# RDF-600.net
KiCad netlist of a schematic drawn in EAGLE
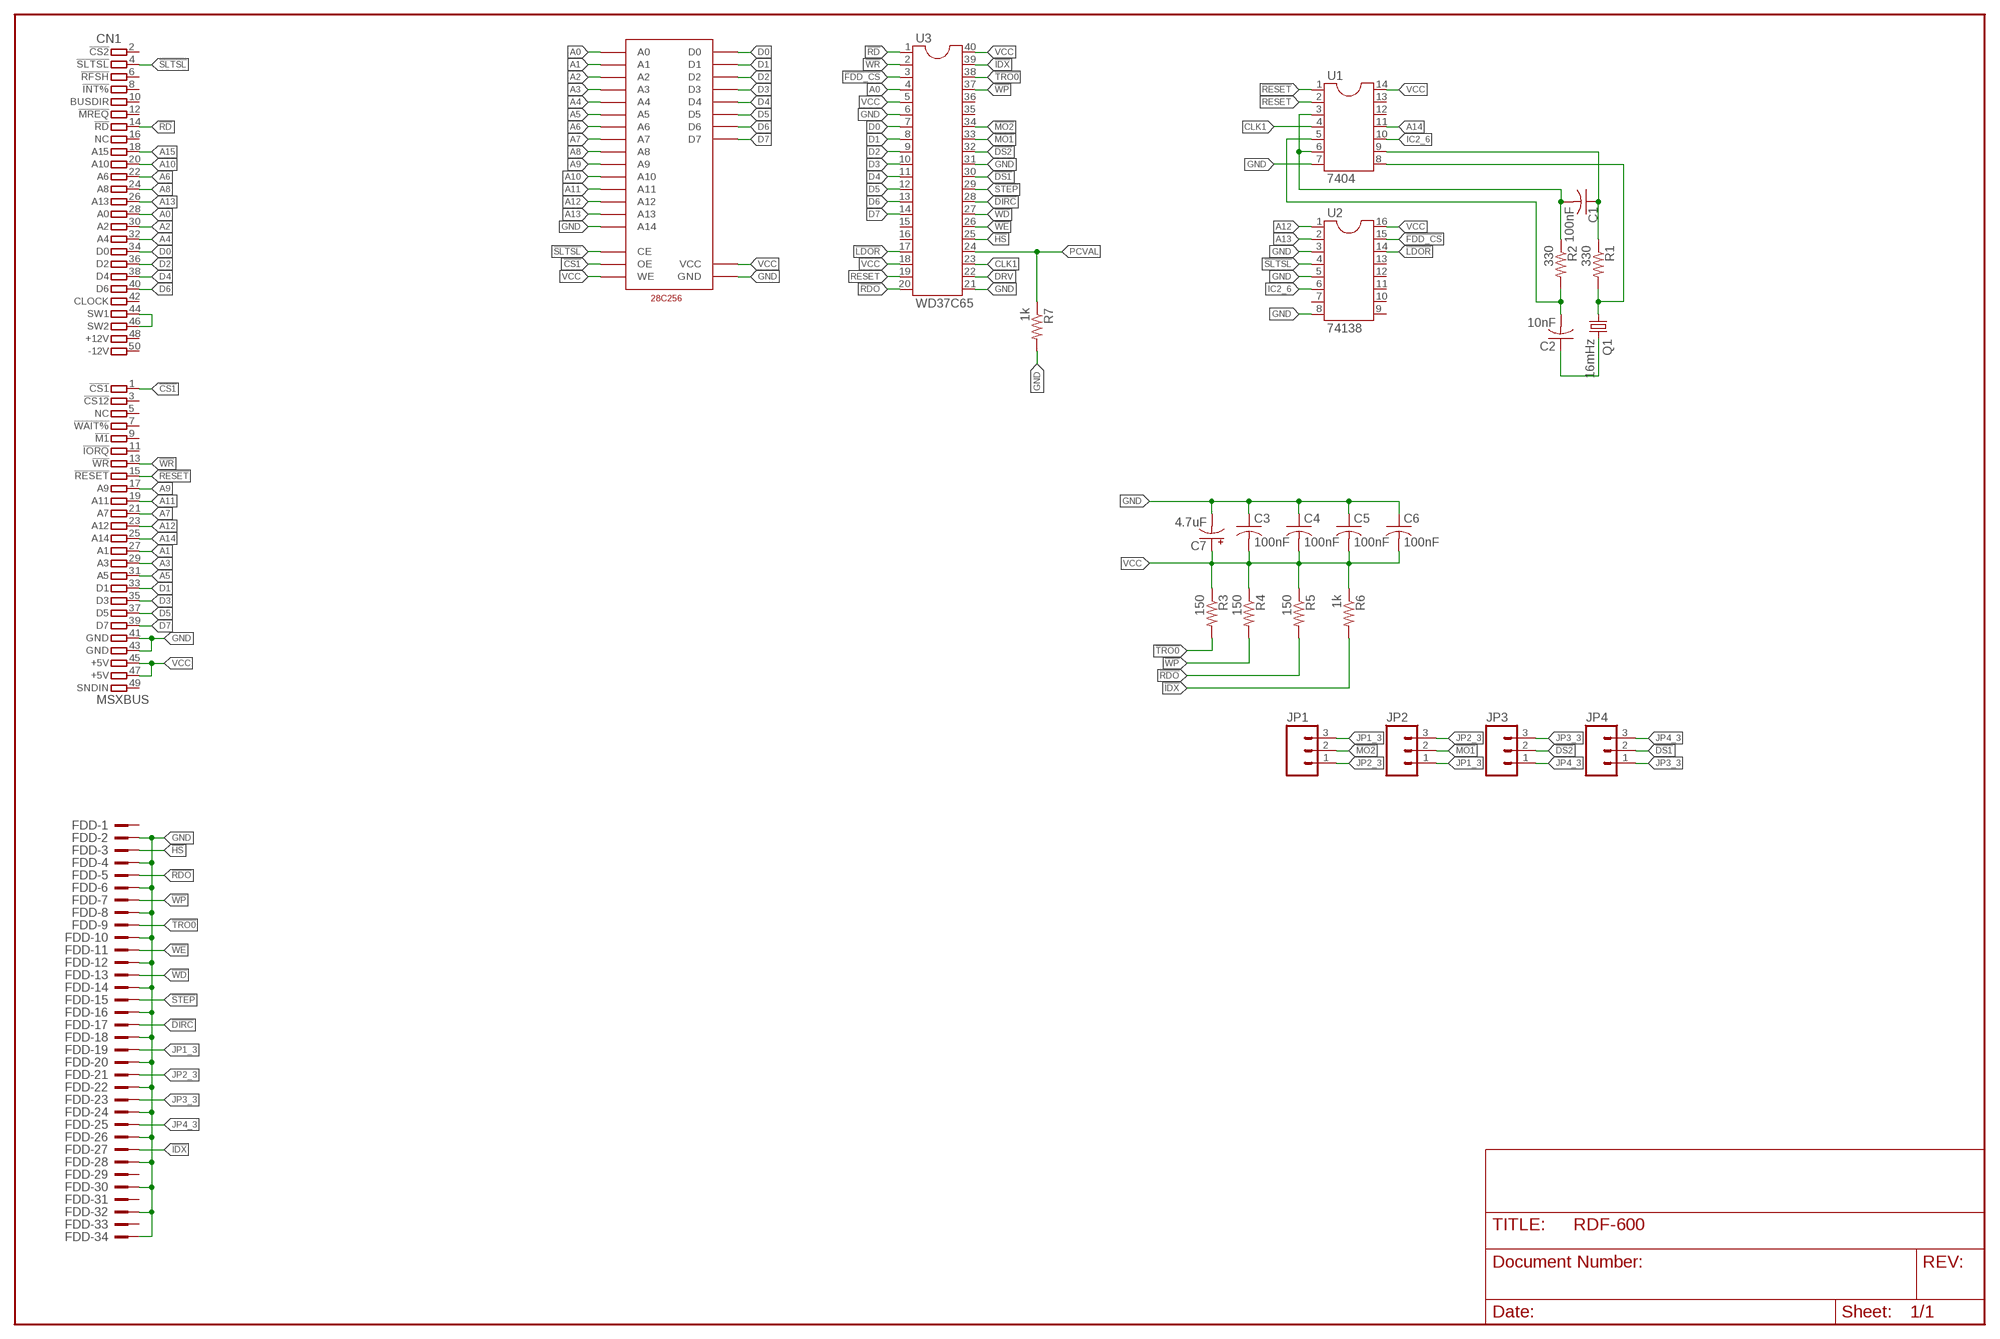
[diagram p0: schematic, sheet 1]

(export (version "E")
  (design (tool "Eeschema 10.0.6"))
  (components
    (comp (ref "28C256")
      (value "28C256")
      (footprint "eagle-import:DIP28")
      (libsource (lib "eagle-import") (part "28C256"))
    )
    (comp (ref "C1")
      (value "100nF")
      (footprint "eagle-import:C025-025X050")
      (libsource (lib "eagle-import") (part "C-US025-025X050"))
    )
    (comp (ref "C2")
      (value "10nF")
      (footprint "eagle-import:C025-025X050")
      (libsource (lib "eagle-import") (part "C-US025-025X050"))
    )
    (comp (ref "C3")
      (value "100nF")
      (footprint "eagle-import:C025-025X050")
      (libsource (lib "eagle-import") (part "C-US025-025X050"))
    )
    (comp (ref "C4")
      (value "100nF")
      (footprint "eagle-import:C025-025X050")
      (libsource (lib "eagle-import") (part "C-US025-025X050"))
    )
    (comp (ref "C5")
      (value "100nF")
      (footprint "eagle-import:C025-025X050")
      (libsource (lib "eagle-import") (part "C-US025-025X050"))
    )
    (comp (ref "C6")
      (value "100nF")
      (footprint "eagle-import:C025-025X050")
      (libsource (lib "eagle-import") (part "C-US025-025X050"))
    )
    (comp (ref "C7")
      (value "4.7uF")
      (footprint "eagle-import:E2,5-6E")
      (libsource (lib "eagle-import") (part "CPOL-USE2,5-6E"))
    )
    (comp (ref "CN1")
      (value "MSXBUS")
      (footprint "eagle-import:MSXBUS_EDGECONN")
      (libsource (lib "eagle-import") (part "MSXBUS_EDGE"))
    )
    (comp (ref "FDD")
      (value "2534-5")
      (footprint "eagle-import:PAK100_2500-5-34")
      (libsource (lib "eagle-import") (part "2534-5"))
    )
    (comp (ref "JP1")
      (value "M03PTH")
      (footprint "eagle-import:1X03")
      (libsource (lib "eagle-import") (part "M03PTH"))
    )
    (comp (ref "JP2")
      (value "M03PTH")
      (footprint "eagle-import:1X03")
      (libsource (lib "eagle-import") (part "M03PTH"))
    )
    (comp (ref "JP3")
      (value "M03PTH")
      (footprint "eagle-import:1X03")
      (libsource (lib "eagle-import") (part "M03PTH"))
    )
    (comp (ref "JP4")
      (value "M03PTH")
      (footprint "eagle-import:1X03")
      (libsource (lib "eagle-import") (part "M03PTH"))
    )
    (comp (ref "Q1")
      (value "16mHz")
      (footprint "eagle-import:HC49_S")
      (libsource (lib "eagle-import") (part "CRYSTALHC49S"))
    )
    (comp (ref "R1")
      (value "330")
      (footprint "eagle-import:0207_7")
      (libsource (lib "eagle-import") (part "R-US_0207/7"))
    )
    (comp (ref "R2")
      (value "330")
      (footprint "eagle-import:0207_7")
      (libsource (lib "eagle-import") (part "R-US_0207/7"))
    )
    (comp (ref "R3")
      (value "150")
      (footprint "eagle-import:0207_7")
      (libsource (lib "eagle-import") (part "R-US_0207/7"))
    )
    (comp (ref "R4")
      (value "150")
      (footprint "eagle-import:0207_7")
      (libsource (lib "eagle-import") (part "R-US_0207/7"))
    )
    (comp (ref "R5")
      (value "150")
      (footprint "eagle-import:0207_7")
      (libsource (lib "eagle-import") (part "R-US_0207/7"))
    )
    (comp (ref "R6")
      (value "1k")
      (footprint "eagle-import:0207_7")
      (libsource (lib "eagle-import") (part "R-US_0207/7"))
    )
    (comp (ref "R7")
      (value "1k")
      (footprint "eagle-import:0207_7")
      (libsource (lib "eagle-import") (part "R-US_0207/7"))
    )
    (comp (ref "U1")
      (value "7404")
      (footprint "eagle-import:DIL14")
      (libsource (lib "eagle-import") (part "DIL14"))
    )
    (comp (ref "U2")
      (value "74138")
      (footprint "eagle-import:DIL16")
      (libsource (lib "eagle-import") (part "DIL16"))
    )
    (comp (ref "U3")
      (value "WD37C65")
      (footprint "eagle-import:DIL40")
      (libsource (lib "eagle-import") (part "DIL40"))
    )
  )
  (nets
    (net (code "1") (name "/~{CS1}") (class "Default")
      (node (ref "28C256") (pin "P$22") (pinfunction "OE_P$22") (pintype "bidirectional"))
      (node (ref "CN1") (pin "1") (pinfunction "1.~{CS1}_1") (pintype "output"))
    )
    (net (code "2") (name "/~{DIRC}") (class "Default")
      (node (ref "FDD") (pin "17") (pinfunction "KL_17") (pintype "passive"))
      (node (ref "U3") (pin "28") (pinfunction "28_28") (pintype "passive"))
    )
    (net (code "3") (name "/~{DS1}") (class "Default")
      (node (ref "JP4") (pin "2") (pinfunction "2_2") (pintype "passive"))
      (node (ref "U3") (pin "30") (pinfunction "30_30") (pintype "passive"))
    )
    (net (code "4") (name "/~{DS2}") (class "Default")
      (node (ref "JP3") (pin "2") (pinfunction "2_2") (pintype "passive"))
      (node (ref "U3") (pin "32") (pinfunction "32_32") (pintype "passive"))
    )
    (net (code "5") (name "/~{FDD_CS}") (class "Default")
      (node (ref "U2") (pin "15") (pinfunction "15_15") (pintype "passive"))
      (node (ref "U3") (pin "3") (pinfunction "3_3") (pintype "passive"))
    )
    (net (code "6") (name "/~{HS}") (class "Default")
      (node (ref "FDD") (pin "3") (pinfunction "KL_3") (pintype "passive"))
      (node (ref "U3") (pin "25") (pinfunction "25_25") (pintype "passive"))
    )
    (net (code "7") (name "/~{IDX}") (class "Default")
      (node (ref "FDD") (pin "27") (pinfunction "KL_27") (pintype "passive"))
      (node (ref "R6") (pin "2") (pinfunction "2_2") (pintype "passive"))
      (node (ref "U3") (pin "39") (pinfunction "39_39") (pintype "passive"))
    )
    (net (code "8") (name "/~{LDOR}") (class "Default")
      (node (ref "U2") (pin "14") (pinfunction "14_14") (pintype "passive"))
      (node (ref "U3") (pin "17") (pinfunction "17_17") (pintype "passive"))
    )
    (net (code "9") (name "/~{MO1}") (class "Default")
      (node (ref "JP2") (pin "2") (pinfunction "2_2") (pintype "passive"))
      (node (ref "U3") (pin "33") (pinfunction "33_33") (pintype "passive"))
    )
    (net (code "10") (name "/~{MO2}") (class "Default")
      (node (ref "JP1") (pin "2") (pinfunction "2_2") (pintype "passive"))
      (node (ref "U3") (pin "34") (pinfunction "34_34") (pintype "passive"))
    )
    (net (code "11") (name "/~{RDO}") (class "Default")
      (node (ref "FDD") (pin "5") (pinfunction "KL_5") (pintype "passive"))
      (node (ref "R5") (pin "2") (pinfunction "2_2") (pintype "passive"))
      (node (ref "U3") (pin "20") (pinfunction "20_20") (pintype "passive"))
    )
    (net (code "12") (name "/~{RD}") (class "Default")
      (node (ref "CN1") (pin "14") (pinfunction "14.~{RD}_14") (pintype "output"))
      (node (ref "U3") (pin "1") (pinfunction "1_1") (pintype "passive"))
    )
    (net (code "13") (name "/~{RESET}") (class "Default")
      (node (ref "CN1") (pin "15") (pinfunction "15.~{RESET}_15") (pintype "output"))
      (node (ref "U1") (pin "1") (pinfunction "1_1") (pintype "passive"))
    )
    (net (code "14") (name "/~{SLTSL}") (class "Default")
      (node (ref "28C256") (pin "P$20") (pinfunction "CE_P$20") (pintype "bidirectional"))
      (node (ref "CN1") (pin "4") (pinfunction "4.~{SLTSL}_4") (pintype "output"))
      (node (ref "U2") (pin "4") (pinfunction "4_4") (pintype "passive"))
    )
    (net (code "15") (name "/~{STEP}") (class "Default")
      (node (ref "FDD") (pin "15") (pinfunction "KL_15") (pintype "passive"))
      (node (ref "U3") (pin "29") (pinfunction "29_29") (pintype "passive"))
    )
    (net (code "16") (name "/~{TRO0}") (class "Default")
      (node (ref "FDD") (pin "9") (pinfunction "KL_9") (pintype "passive"))
      (node (ref "R3") (pin "2") (pinfunction "2_2") (pintype "passive"))
      (node (ref "U3") (pin "38") (pinfunction "38_38") (pintype "passive"))
    )
    (net (code "17") (name "/~{WD}") (class "Default")
      (node (ref "FDD") (pin "13") (pinfunction "KL_13") (pintype "passive"))
      (node (ref "U3") (pin "27") (pinfunction "27_27") (pintype "passive"))
    )
    (net (code "18") (name "/~{WE}") (class "Default")
      (node (ref "FDD") (pin "11") (pinfunction "KL_11") (pintype "passive"))
      (node (ref "U3") (pin "26") (pinfunction "26_26") (pintype "passive"))
    )
    (net (code "19") (name "/~{WP}") (class "Default")
      (node (ref "FDD") (pin "7") (pinfunction "KL_7") (pintype "passive"))
      (node (ref "R4") (pin "2") (pinfunction "2_2") (pintype "passive"))
      (node (ref "U3") (pin "37") (pinfunction "37_37") (pintype "passive"))
    )
    (net (code "20") (name "/~{WR}") (class "Default")
      (node (ref "CN1") (pin "13") (pinfunction "13.~{WR}_13") (pintype "output"))
      (node (ref "U3") (pin "2") (pinfunction "2_2") (pintype "passive"))
    )
    (net (code "21") (name "A0") (class "Default")
      (node (ref "28C256") (pin "P$10") (pinfunction "A0_P$10") (pintype "bidirectional"))
      (node (ref "CN1") (pin "28") (pinfunction "28.A0_28") (pintype "output"))
      (node (ref "U3") (pin "4") (pinfunction "4_4") (pintype "passive"))
    )
    (net (code "22") (name "A1") (class "Default")
      (node (ref "28C256") (pin "P$9") (pinfunction "A1_P$9") (pintype "bidirectional"))
      (node (ref "CN1") (pin "27") (pinfunction "27.A1_27") (pintype "output"))
    )
    (net (code "23") (name "A2") (class "Default")
      (node (ref "28C256") (pin "P$8") (pinfunction "A2_P$8") (pintype "bidirectional"))
      (node (ref "CN1") (pin "30") (pinfunction "30.A2_30") (pintype "output"))
    )
    (net (code "24") (name "A3") (class "Default")
      (node (ref "28C256") (pin "P$7") (pinfunction "A3_P$7") (pintype "bidirectional"))
      (node (ref "CN1") (pin "29") (pinfunction "29.A3_29") (pintype "output"))
    )
    (net (code "25") (name "A4") (class "Default")
      (node (ref "28C256") (pin "P$6") (pinfunction "A4_P$6") (pintype "bidirectional"))
      (node (ref "CN1") (pin "32") (pinfunction "32.A4_32") (pintype "output"))
    )
    (net (code "26") (name "A5") (class "Default")
      (node (ref "28C256") (pin "P$5") (pinfunction "A5_P$5") (pintype "bidirectional"))
      (node (ref "CN1") (pin "31") (pinfunction "31.A5_31") (pintype "output"))
    )
    (net (code "27") (name "A6") (class "Default")
      (node (ref "28C256") (pin "P$4") (pinfunction "A6_P$4") (pintype "bidirectional"))
      (node (ref "CN1") (pin "22") (pinfunction "22.A6_22") (pintype "output"))
    )
    (net (code "28") (name "A7") (class "Default")
      (node (ref "28C256") (pin "P$3") (pinfunction "A7_P$3") (pintype "bidirectional"))
      (node (ref "CN1") (pin "21") (pinfunction "21.A7_21") (pintype "output"))
    )
    (net (code "29") (name "A8") (class "Default")
      (node (ref "28C256") (pin "P$25") (pinfunction "A8_P$25") (pintype "bidirectional"))
      (node (ref "CN1") (pin "24") (pinfunction "24.A8_24") (pintype "output"))
    )
    (net (code "30") (name "A9") (class "Default")
      (node (ref "28C256") (pin "P$24") (pinfunction "A9_P$24") (pintype "bidirectional"))
      (node (ref "CN1") (pin "17") (pinfunction "17.A9_17") (pintype "output"))
    )
    (net (code "31") (name "A10") (class "Default")
      (node (ref "28C256") (pin "P$21") (pinfunction "A10_P$21") (pintype "bidirectional"))
      (node (ref "CN1") (pin "20") (pinfunction "20.A10_20") (pintype "output"))
    )
    (net (code "32") (name "A11") (class "Default")
      (node (ref "28C256") (pin "P$23") (pinfunction "A11_P$23") (pintype "bidirectional"))
      (node (ref "CN1") (pin "19") (pinfunction "19.A11_19") (pintype "output"))
    )
    (net (code "33") (name "A12") (class "Default")
      (node (ref "28C256") (pin "P$2") (pinfunction "A12_P$2") (pintype "bidirectional"))
      (node (ref "CN1") (pin "23") (pinfunction "23.A12_23") (pintype "output"))
      (node (ref "U2") (pin "1") (pinfunction "1_1") (pintype "passive"))
    )
    (net (code "34") (name "A13") (class "Default")
      (node (ref "28C256") (pin "P$26") (pinfunction "A13_P$26") (pintype "bidirectional"))
      (node (ref "CN1") (pin "26") (pinfunction "26.A13_26") (pintype "output"))
      (node (ref "U2") (pin "2") (pinfunction "2_2") (pintype "passive"))
    )
    (net (code "35") (name "A14") (class "Default")
      (node (ref "CN1") (pin "25") (pinfunction "25.A14_25") (pintype "output"))
      (node (ref "U1") (pin "11") (pinfunction "11_11") (pintype "passive"))
    )
    (net (code "36") (name "A15") (class "Default")
      (node (ref "CN1") (pin "18") (pinfunction "18.A15_18") (pintype "output"))
    )
    (net (code "37") (name "CLK1") (class "Default")
      (node (ref "U1") (pin "4") (pinfunction "4_4") (pintype "passive"))
      (node (ref "U3") (pin "23") (pinfunction "23_23") (pintype "passive"))
    )
    (net (code "38") (name "D0") (class "Default")
      (node (ref "28C256") (pin "P$11") (pinfunction "D0_P$11") (pintype "bidirectional"))
      (node (ref "CN1") (pin "34") (pinfunction "34.D0_34") (pintype "bidirectional"))
      (node (ref "U3") (pin "7") (pinfunction "7_7") (pintype "passive"))
    )
    (net (code "39") (name "D1") (class "Default")
      (node (ref "28C256") (pin "P$12") (pinfunction "D1_P$12") (pintype "bidirectional"))
      (node (ref "CN1") (pin "33") (pinfunction "33.D1_33") (pintype "bidirectional"))
      (node (ref "U3") (pin "8") (pinfunction "8_8") (pintype "passive"))
    )
    (net (code "40") (name "D2") (class "Default")
      (node (ref "28C256") (pin "P$13") (pinfunction "D2_P$13") (pintype "bidirectional"))
      (node (ref "CN1") (pin "36") (pinfunction "36.D2_36") (pintype "bidirectional"))
      (node (ref "U3") (pin "9") (pinfunction "9_9") (pintype "passive"))
    )
    (net (code "41") (name "D3") (class "Default")
      (node (ref "28C256") (pin "P$15") (pinfunction "D3_P$15") (pintype "bidirectional"))
      (node (ref "CN1") (pin "35") (pinfunction "35.D3_35") (pintype "bidirectional"))
      (node (ref "U3") (pin "10") (pinfunction "10_10") (pintype "passive"))
    )
    (net (code "42") (name "D4") (class "Default")
      (node (ref "28C256") (pin "P$16") (pinfunction "D4_P$16") (pintype "bidirectional"))
      (node (ref "CN1") (pin "38") (pinfunction "38.D4_38") (pintype "bidirectional"))
      (node (ref "U3") (pin "11") (pinfunction "11_11") (pintype "passive"))
    )
    (net (code "43") (name "D5") (class "Default")
      (node (ref "28C256") (pin "P$17") (pinfunction "D5_P$17") (pintype "bidirectional"))
      (node (ref "CN1") (pin "37") (pinfunction "37.D5_37") (pintype "bidirectional"))
      (node (ref "U3") (pin "12") (pinfunction "12_12") (pintype "passive"))
    )
    (net (code "44") (name "D6") (class "Default")
      (node (ref "28C256") (pin "P$18") (pinfunction "D6_P$18") (pintype "bidirectional"))
      (node (ref "CN1") (pin "40") (pinfunction "40.D6_40") (pintype "bidirectional"))
      (node (ref "U3") (pin "13") (pinfunction "13_13") (pintype "passive"))
    )
    (net (code "45") (name "D7") (class "Default")
      (node (ref "28C256") (pin "P$19") (pinfunction "D7_P$19") (pintype "bidirectional"))
      (node (ref "CN1") (pin "39") (pinfunction "39.D7_39") (pintype "bidirectional"))
      (node (ref "U3") (pin "14") (pinfunction "14_14") (pintype "passive"))
    )
    (net (code "46") (name "DRV") (class "Default")
      (node (ref "U3") (pin "22") (pinfunction "22_22") (pintype "passive"))
    )
    (net (code "47") (name "GND") (class "Default")
      (node (ref "28C256") (pin "P$1") (pinfunction "A14_P$1") (pintype "bidirectional"))
      (node (ref "28C256") (pin "P$14") (pinfunction "GND_P$14") (pintype "bidirectional"))
      (node (ref "C3") (pin "1") (pinfunction "1_1") (pintype "passive"))
      (node (ref "C4") (pin "1") (pinfunction "1_1") (pintype "passive"))
      (node (ref "C5") (pin "1") (pinfunction "1_1") (pintype "passive"))
      (node (ref "C6") (pin "1") (pinfunction "1_1") (pintype "passive"))
      (node (ref "C7") (pin "-") (pinfunction "-_-") (pintype "passive"))
      (node (ref "CN1") (pin "41") (pinfunction "41.GND_41") (pintype "passive"))
      (node (ref "CN1") (pin "43") (pinfunction "43.GND_43") (pintype "passive"))
      (node (ref "FDD") (pin "10") (pinfunction "KL_10") (pintype "passive"))
      (node (ref "FDD") (pin "12") (pinfunction "KL_12") (pintype "passive"))
      (node (ref "FDD") (pin "14") (pinfunction "KL_14") (pintype "passive"))
      (node (ref "FDD") (pin "16") (pinfunction "KL_16") (pintype "passive"))
      (node (ref "FDD") (pin "18") (pinfunction "KL_18") (pintype "passive"))
      (node (ref "FDD") (pin "2") (pinfunction "KL_2") (pintype "passive"))
      (node (ref "FDD") (pin "20") (pinfunction "KL_20") (pintype "passive"))
      (node (ref "FDD") (pin "22") (pinfunction "KL_22") (pintype "passive"))
      (node (ref "FDD") (pin "24") (pinfunction "KL_24") (pintype "passive"))
      (node (ref "FDD") (pin "26") (pinfunction "KL_26") (pintype "passive"))
      (node (ref "FDD") (pin "28") (pinfunction "KL_28") (pintype "passive"))
      (node (ref "FDD") (pin "30") (pinfunction "KL_30") (pintype "passive"))
      (node (ref "FDD") (pin "32") (pinfunction "KL_32") (pintype "passive"))
      (node (ref "FDD") (pin "34") (pinfunction "KL_34") (pintype "passive"))
      (node (ref "FDD") (pin "4") (pinfunction "KL_4") (pintype "passive"))
      (node (ref "FDD") (pin "6") (pinfunction "KL_6") (pintype "passive"))
      (node (ref "FDD") (pin "8") (pinfunction "KL_8") (pintype "passive"))
      (node (ref "R7") (pin "2") (pinfunction "2_2") (pintype "passive"))
      (node (ref "U1") (pin "7") (pinfunction "7_7") (pintype "passive"))
      (node (ref "U2") (pin "3") (pinfunction "3_3") (pintype "passive"))
      (node (ref "U2") (pin "5") (pinfunction "5_5") (pintype "passive"))
      (node (ref "U2") (pin "8") (pinfunction "8_8") (pintype "passive"))
      (node (ref "U3") (pin "21") (pinfunction "21_21") (pintype "passive"))
      (node (ref "U3") (pin "31") (pinfunction "31_31") (pintype "passive"))
      (node (ref "U3") (pin "6") (pinfunction "6_6") (pintype "passive"))
    )
    (net (code "48") (name "IC2_6") (class "Default")
      (node (ref "U1") (pin "10") (pinfunction "10_10") (pintype "passive"))
      (node (ref "U2") (pin "6") (pinfunction "6_6") (pintype "passive"))
    )
    (net (code "49") (name "JP1_3") (class "Default")
      (node (ref "FDD") (pin "19") (pinfunction "KL_19") (pintype "passive"))
      (node (ref "JP1") (pin "3") (pinfunction "3_3") (pintype "passive"))
      (node (ref "JP2") (pin "1") (pinfunction "1_1") (pintype "passive"))
    )
    (net (code "50") (name "JP2_3") (class "Default")
      (node (ref "FDD") (pin "21") (pinfunction "KL_21") (pintype "passive"))
      (node (ref "JP1") (pin "1") (pinfunction "1_1") (pintype "passive"))
      (node (ref "JP2") (pin "3") (pinfunction "3_3") (pintype "passive"))
    )
    (net (code "51") (name "JP3_3") (class "Default")
      (node (ref "FDD") (pin "23") (pinfunction "KL_23") (pintype "passive"))
      (node (ref "JP3") (pin "3") (pinfunction "3_3") (pintype "passive"))
      (node (ref "JP4") (pin "1") (pinfunction "1_1") (pintype "passive"))
    )
    (net (code "52") (name "JP4_3") (class "Default")
      (node (ref "FDD") (pin "25") (pinfunction "KL_25") (pintype "passive"))
      (node (ref "JP3") (pin "1") (pinfunction "1_1") (pintype "passive"))
      (node (ref "JP4") (pin "3") (pinfunction "3_3") (pintype "passive"))
    )
    (net (code "53") (name "Net-(C1-Pad1)") (class "Default")
      (node (ref "C1") (pin "1") (pinfunction "1_1") (pintype "passive"))
      (node (ref "R1") (pin "1") (pinfunction "1_1") (pintype "passive"))
      (node (ref "U1") (pin "9") (pinfunction "9_9") (pintype "passive"))
    )
    (net (code "54") (name "Net-(C1-Pad2)") (class "Default")
      (node (ref "C1") (pin "2") (pinfunction "2_2") (pintype "passive"))
      (node (ref "R2") (pin "1") (pinfunction "1_1") (pintype "passive"))
      (node (ref "U1") (pin "3") (pinfunction "3_3") (pintype "passive"))
      (node (ref "U1") (pin "6") (pinfunction "6_6") (pintype "passive"))
    )
    (net (code "55") (name "Net-(C2-Pad1)") (class "Default")
      (node (ref "C2") (pin "1") (pinfunction "1_1") (pintype "passive"))
      (node (ref "Q1") (pin "2") (pinfunction "2_2") (pintype "passive"))
    )
    (net (code "56") (name "Net-(C2-Pad2)") (class "Default")
      (node (ref "C2") (pin "2") (pinfunction "2_2") (pintype "passive"))
      (node (ref "R2") (pin "2") (pinfunction "2_2") (pintype "passive"))
      (node (ref "U1") (pin "5") (pinfunction "5_5") (pintype "passive"))
    )
    (net (code "57") (name "Net-(CN1-44.SW1)") (class "Default")
      (node (ref "CN1") (pin "44") (pinfunction "44.SW1_44") (pintype "passive"))
      (node (ref "CN1") (pin "46") (pinfunction "46.SW2_46") (pintype "passive"))
    )
    (net (code "58") (name "Net-(Q1-Pad1)") (class "Default")
      (node (ref "Q1") (pin "1") (pinfunction "1_1") (pintype "passive"))
      (node (ref "R1") (pin "2") (pinfunction "2_2") (pintype "passive"))
      (node (ref "U1") (pin "8") (pinfunction "8_8") (pintype "passive"))
    )
    (net (code "59") (name "PCVAL") (class "Default")
      (node (ref "R7") (pin "1") (pinfunction "1_1") (pintype "passive"))
      (node (ref "U3") (pin "24") (pinfunction "24_24") (pintype "passive"))
    )
    (net (code "60") (name "RESET") (class "Default")
      (node (ref "U1") (pin "2") (pinfunction "2_2") (pintype "passive"))
      (node (ref "U3") (pin "19") (pinfunction "19_19") (pintype "passive"))
    )
    (net (code "61") (name "VCC") (class "Default")
      (node (ref "28C256") (pin "P$27") (pinfunction "WE_P$27") (pintype "bidirectional"))
      (node (ref "28C256") (pin "P$28") (pinfunction "VCC_P$28") (pintype "bidirectional"))
      (node (ref "C3") (pin "2") (pinfunction "2_2") (pintype "passive"))
      (node (ref "C4") (pin "2") (pinfunction "2_2") (pintype "passive"))
      (node (ref "C5") (pin "2") (pinfunction "2_2") (pintype "passive"))
      (node (ref "C6") (pin "2") (pinfunction "2_2") (pintype "passive"))
      (node (ref "C7") (pin "+") (pinfunction "+_+") (pintype "passive"))
      (node (ref "CN1") (pin "45") (pinfunction "45.+5V_45") (pintype "passive"))
      (node (ref "CN1") (pin "47") (pinfunction "47.+5V_47") (pintype "passive"))
      (node (ref "R3") (pin "1") (pinfunction "1_1") (pintype "passive"))
      (node (ref "R4") (pin "1") (pinfunction "1_1") (pintype "passive"))
      (node (ref "R5") (pin "1") (pinfunction "1_1") (pintype "passive"))
      (node (ref "R6") (pin "1") (pinfunction "1_1") (pintype "passive"))
      (node (ref "U1") (pin "14") (pinfunction "14_14") (pintype "passive"))
      (node (ref "U2") (pin "16") (pinfunction "16_16") (pintype "passive"))
      (node (ref "U3") (pin "18") (pinfunction "18_18") (pintype "passive"))
      (node (ref "U3") (pin "40") (pinfunction "40_40") (pintype "passive"))
      (node (ref "U3") (pin "5") (pinfunction "5_5") (pintype "passive"))
    )
    (net (code "62") (name "unconnected-(CN1-2.~{CS2}-Pad2)") (class "Default")
      (node (ref "CN1") (pin "2") (pinfunction "2.~{CS2}_2") (pintype "output"))
    )
    (net (code "63") (name "unconnected-(CN1-3.~{CS12}-Pad3)") (class "Default")
      (node (ref "CN1") (pin "3") (pinfunction "3.~{CS12}_3") (pintype "output"))
    )
    (net (code "64") (name "unconnected-(CN1-5.NC-Pad5)") (class "Default")
      (node (ref "CN1") (pin "5") (pinfunction "5.NC_5") (pintype "no_connect"))
    )
    (net (code "65") (name "unconnected-(CN1-6.~{RFSH}-Pad6)") (class "Default")
      (node (ref "CN1") (pin "6") (pinfunction "6.~{RFSH}_6") (pintype "output"))
    )
    (net (code "66") (name "unconnected-(CN1-7.~{WAIT%}-Pad7)") (class "Default")
      (node (ref "CN1") (pin "7") (pinfunction "7.~{WAIT%}_7") (pintype "open_collector"))
    )
    (net (code "67") (name "unconnected-(CN1-8.~{INT%}-Pad8)") (class "Default")
      (node (ref "CN1") (pin "8") (pinfunction "8.~{INT%}_8") (pintype "open_collector"))
    )
    (net (code "68") (name "unconnected-(CN1-9.~{M1}-Pad9)") (class "Default")
      (node (ref "CN1") (pin "9") (pinfunction "9.~{M1}_9") (pintype "output"))
    )
    (net (code "69") (name "unconnected-(CN1-10.BUSDIR-Pad10)") (class "Default")
      (node (ref "CN1") (pin "10") (pinfunction "10.BUSDIR_10") (pintype "open_collector"))
    )
    (net (code "70") (name "unconnected-(CN1-11.~{IORQ}-Pad11)") (class "Default")
      (node (ref "CN1") (pin "11") (pinfunction "11.~{IORQ}_11") (pintype "output"))
    )
    (net (code "71") (name "unconnected-(CN1-12.~{MREQ}-Pad12)") (class "Default")
      (node (ref "CN1") (pin "12") (pinfunction "12.~{MREQ}_12") (pintype "output"))
    )
    (net (code "72") (name "unconnected-(CN1-16.NC-Pad16)") (class "Default")
      (node (ref "CN1") (pin "16") (pinfunction "16.NC_16") (pintype "no_connect"))
    )
    (net (code "73") (name "unconnected-(CN1-42.CLOCK-Pad42)") (class "Default")
      (node (ref "CN1") (pin "42") (pinfunction "42.CLOCK_42") (pintype "output"))
    )
    (net (code "74") (name "unconnected-(CN1-48.+12V-Pad48)") (class "Default")
      (node (ref "CN1") (pin "48") (pinfunction "48.+12V_48") (pintype "passive"))
    )
    (net (code "75") (name "unconnected-(CN1-49.SNDIN-Pad49)") (class "Default")
      (node (ref "CN1") (pin "49") (pinfunction "49.SNDIN_49") (pintype "open_collector"))
    )
    (net (code "76") (name "unconnected-(CN1-50.-12V-Pad50)") (class "Default")
      (node (ref "CN1") (pin "50") (pinfunction "50.-12V_50") (pintype "passive"))
    )
    (net (code "77") (name "unconnected-(FDDA-KL-Pad1)") (class "Default")
      (node (ref "FDD") (pin "1") (pinfunction "KL_1") (pintype "passive"))
    )
    (net (code "78") (name "unconnected-(FDDAA-KL-Pad33)") (class "Default")
      (node (ref "FDD") (pin "33") (pinfunction "KL_33") (pintype "passive"))
    )
    (net (code "79") (name "unconnected-(FDDV-KL-Pad29)") (class "Default")
      (node (ref "FDD") (pin "29") (pinfunction "KL_29") (pintype "passive"))
    )
    (net (code "80") (name "unconnected-(FDDY-KL-Pad31)") (class "Default")
      (node (ref "FDD") (pin "31") (pinfunction "KL_31") (pintype "passive"))
    )
    (net (code "81") (name "unconnected-(U1-Pad12)") (class "Default")
      (node (ref "U1") (pin "12") (pinfunction "12_12") (pintype "passive"))
    )
    (net (code "82") (name "unconnected-(U1-Pad13)") (class "Default")
      (node (ref "U1") (pin "13") (pinfunction "13_13") (pintype "passive"))
    )
    (net (code "83") (name "unconnected-(U2-Pad7)") (class "Default")
      (node (ref "U2") (pin "7") (pinfunction "7_7") (pintype "passive"))
    )
    (net (code "84") (name "unconnected-(U2-Pad9)") (class "Default")
      (node (ref "U2") (pin "9") (pinfunction "9_9") (pintype "passive"))
    )
    (net (code "85") (name "unconnected-(U2-Pad10)") (class "Default")
      (node (ref "U2") (pin "10") (pinfunction "10_10") (pintype "passive"))
    )
    (net (code "86") (name "unconnected-(U2-Pad11)") (class "Default")
      (node (ref "U2") (pin "11") (pinfunction "11_11") (pintype "passive"))
    )
    (net (code "87") (name "unconnected-(U2-Pad12)") (class "Default")
      (node (ref "U2") (pin "12") (pinfunction "12_12") (pintype "passive"))
    )
    (net (code "88") (name "unconnected-(U2-Pad13)") (class "Default")
      (node (ref "U2") (pin "13") (pinfunction "13_13") (pintype "passive"))
    )
    (net (code "89") (name "unconnected-(U3-Pad15)") (class "Default")
      (node (ref "U3") (pin "15") (pinfunction "15_15") (pintype "passive"))
    )
    (net (code "90") (name "unconnected-(U3-Pad16)") (class "Default")
      (node (ref "U3") (pin "16") (pinfunction "16_16") (pintype "passive"))
    )
    (net (code "91") (name "unconnected-(U3-Pad35)") (class "Default")
      (node (ref "U3") (pin "35") (pinfunction "35_35") (pintype "passive"))
    )
    (net (code "92") (name "unconnected-(U3-Pad36)") (class "Default")
      (node (ref "U3") (pin "36") (pinfunction "36_36") (pintype "passive"))
    )
  )
)
